# LD0.net
KiCad netlist of a schematic drawn in Altium Designer
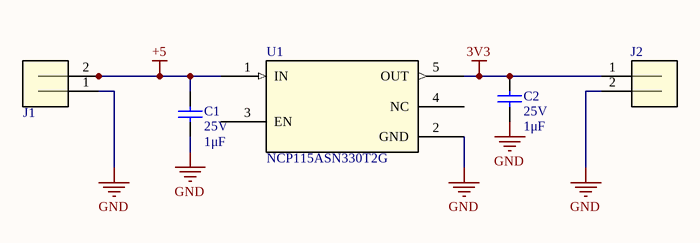
[diagram p0: LD0.SchDoc]

(export (version "E")
  (design (tool "Eeschema 10.0.6"))
  (components
    (comp (ref "C1")
      (value "1μF")
      (footprint "CAP0805")
      (description "CAP CER 1UF 25V X7R 0805")
      (fields (field (name "VOLTAGE RATING") "25V") (field (name "Comment") "GCM21BR71E105KA56L"))
      (libsource (lib "Bootcamp_Schematic_Library (1)") (part "GCM21BR71E105KA56L"))
    )
    (comp (ref "C2")
      (value "1μF")
      (footprint "CAP0805")
      (description "CAP CER 1UF 25V X7R 0805")
      (fields (field (name "VOLTAGE RATING") "25V") (field (name "Comment") "GCM21BR71E105KA56L"))
      (libsource (lib "Bootcamp_Schematic_Library (1)") (part "GCM21BR71E105KA56L"))
    )
    (comp (ref "J1")
      (value "22053021")
      (footprint "CONN2_5-3021_MOL")
      (description "No Description Available")
      (libsource (lib "") (part "22053021_1"))
    )
    (comp (ref "J2")
      (value "22053021")
      (footprint "CONN2_5-3021_MOL")
      (description "No Description Available")
      (libsource (lib "22053021") (part "22053021"))
    )
    (comp (ref "U1")
      (value "NCP115ASN330T2G")
      (footprint "TSOP-5-483-N_ONS")
      (description "No Description Available")
      (libsource (lib "NCP115ASN330T2G") (part "NCP115ASN330T2G"))
    )
  )
  (nets
    (net (code "1") (name "+5") (class "Default")
      (node (ref "C1") (pin "2") (pinfunction "2_2") (pintype "passive"))
      (node (ref "J1") (pin "2") (pinfunction "2_2") (pintype "passive"))
      (node (ref "U1") (pin "1") (pinfunction "IN_1") (pintype "input"))
    )
    (net (code "2") (name "3V3") (class "Default")
      (node (ref "C2") (pin "2") (pinfunction "2_2") (pintype "passive"))
      (node (ref "J2") (pin "1") (pinfunction "1_1") (pintype "passive"))
      (node (ref "U1") (pin "5") (pinfunction "OUT_5") (pintype "output"))
    )
    (net (code "3") (name "GND") (class "Default")
      (node (ref "C1") (pin "1") (pinfunction "1_1") (pintype "passive"))
      (node (ref "C2") (pin "1") (pinfunction "1_1") (pintype "passive"))
      (node (ref "J1") (pin "1") (pinfunction "1_1") (pintype "passive"))
      (node (ref "J2") (pin "2") (pinfunction "2_2") (pintype "passive"))
      (node (ref "U1") (pin "2") (pinfunction "GND_2") (pintype "power_in"))
    )
    (net (code "4") (name "unconnected-(U1-EN-Pad3)") (class "Default")
      (node (ref "U1") (pin "3") (pinfunction "EN_3") (pintype "passive"))
    )
    (net (code "5") (name "unconnected-(U1-NC-Pad4)") (class "Default")
      (node (ref "U1") (pin "4") (pinfunction "NC_4") (pintype "passive"))
    )
  )
)
